# parport.net
KiCad netlist of a schematic drawn in EAGLE
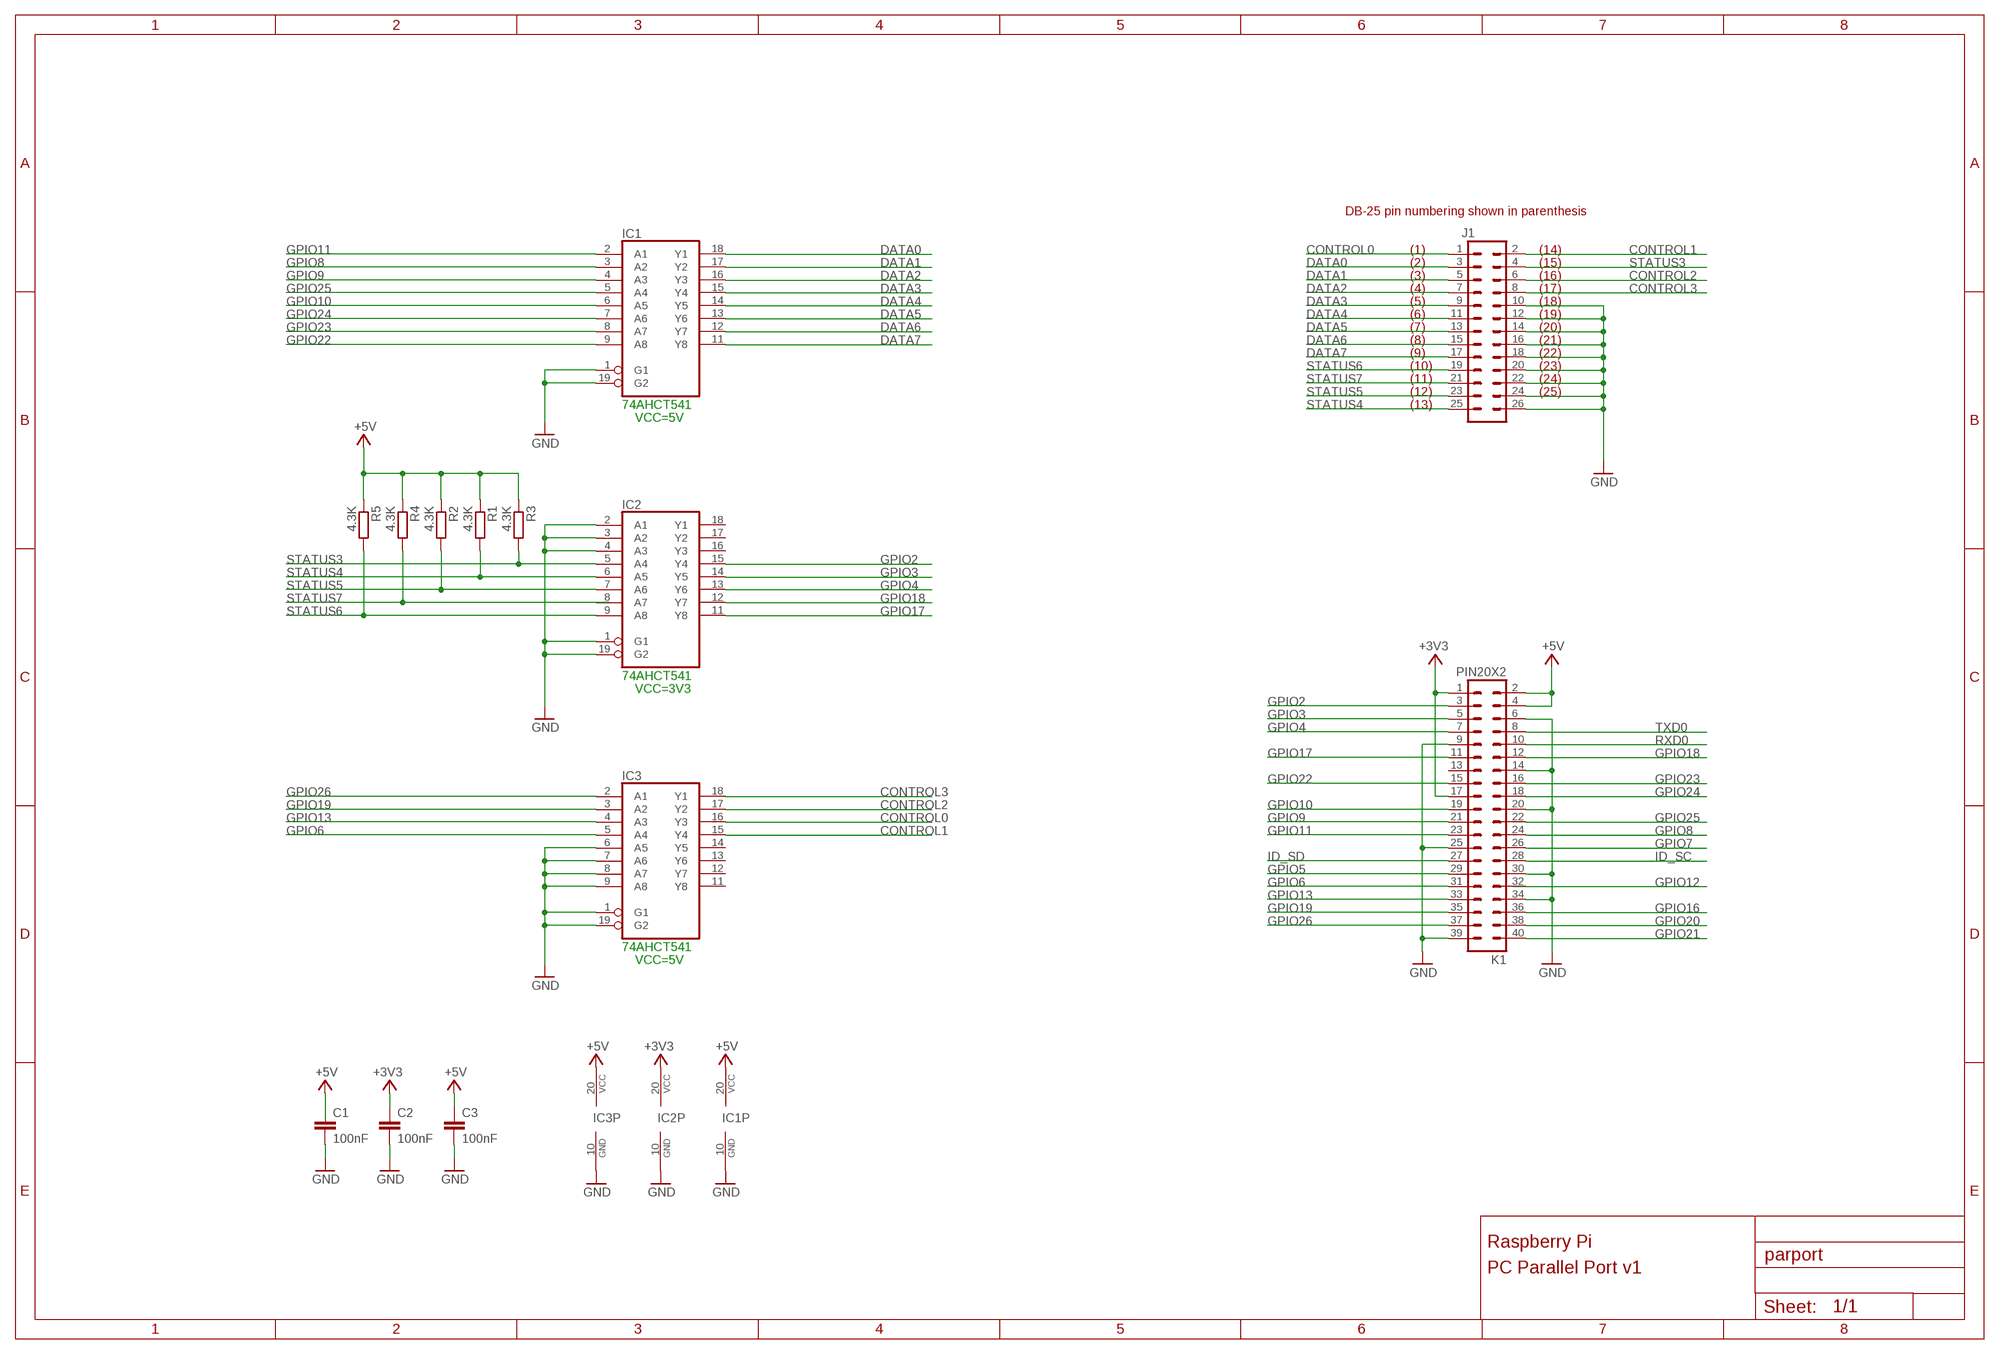
[diagram p0: schematic, sheet 1]

(export (version "E")
  (design (tool "Eeschema 10.0.6"))
  (components
    (comp (ref "C1")
      (value "100nF")
      (footprint "eagle-import:C0805")
      (libsource (lib "eagle-import") (part "C-EUC0805"))
    )
    (comp (ref "C2")
      (value "100nF")
      (footprint "eagle-import:C0805")
      (libsource (lib "eagle-import") (part "C-EUC0805"))
    )
    (comp (ref "C3")
      (value "100nF")
      (footprint "eagle-import:C0805")
      (libsource (lib "eagle-import") (part "C-EUC0805"))
    )
    (comp (ref "IC1")
      (value "74LS541DW")
      (footprint "eagle-import:SO20W")
      (libsource (lib "eagle-import") (part "74541DWLS"))
    )
    (comp (ref "IC2")
      (value "74LS541DW")
      (footprint "eagle-import:SO20W")
      (libsource (lib "eagle-import") (part "74541DWLS"))
    )
    (comp (ref "IC3")
      (value "74LS541DW")
      (footprint "eagle-import:SO20W")
      (libsource (lib "eagle-import") (part "74541DWLS"))
    )
    (comp (ref "J1")
      (value "M13X22X13")
      (footprint "eagle-import:2X13")
      (libsource (lib "eagle-import") (part "M13X22X13"))
    )
    (comp (ref "K1")
      (value "PIN20X2")
      (footprint "eagle-import:PIN_20X2")
      (libsource (lib "eagle-import") (part "PIN20X2"))
    )
    (comp (ref "R1")
      (value "4.3K")
      (footprint "eagle-import:R0805")
      (libsource (lib "eagle-import") (part "R-EU_R0805"))
    )
    (comp (ref "R2")
      (value "4.3K")
      (footprint "eagle-import:R0805")
      (libsource (lib "eagle-import") (part "R-EU_R0805"))
    )
    (comp (ref "R3")
      (value "4.3K")
      (footprint "eagle-import:R0805")
      (libsource (lib "eagle-import") (part "R-EU_R0805"))
    )
    (comp (ref "R4")
      (value "4.3K")
      (footprint "eagle-import:R0805")
      (libsource (lib "eagle-import") (part "R-EU_R0805"))
    )
    (comp (ref "R5")
      (value "4.3K")
      (footprint "eagle-import:R0805")
      (libsource (lib "eagle-import") (part "R-EU_R0805"))
    )
  )
  (nets
    (net (code "1") (name "+3V3") (class "Default")
      (node (ref "C2") (pin "1") (pinfunction "1_1") (pintype "passive"))
      (node (ref "IC2") (pin "20") (pinfunction "VCC_20") (pintype "power_in"))
      (node (ref "K1") (pin "1") (pinfunction "1_1") (pintype "passive"))
      (node (ref "K1") (pin "17") (pinfunction "17_17") (pintype "passive"))
    )
    (net (code "2") (name "+5V") (class "Default")
      (node (ref "C1") (pin "1") (pinfunction "1_1") (pintype "passive"))
      (node (ref "C3") (pin "1") (pinfunction "1_1") (pintype "passive"))
      (node (ref "IC1") (pin "20") (pinfunction "VCC_20") (pintype "power_in"))
      (node (ref "IC3") (pin "20") (pinfunction "VCC_20") (pintype "power_in"))
      (node (ref "K1") (pin "2") (pinfunction "2_2") (pintype "passive"))
      (node (ref "K1") (pin "4") (pinfunction "4_4") (pintype "passive"))
      (node (ref "R1") (pin "1") (pinfunction "1_1") (pintype "passive"))
      (node (ref "R2") (pin "1") (pinfunction "1_1") (pintype "passive"))
      (node (ref "R3") (pin "1") (pinfunction "1_1") (pintype "passive"))
      (node (ref "R4") (pin "1") (pinfunction "1_1") (pintype "passive"))
      (node (ref "R5") (pin "1") (pinfunction "1_1") (pintype "passive"))
    )
    (net (code "3") (name "/CONTROL0") (class "Default")
      (node (ref "IC3") (pin "16") (pinfunction "Y3_16") (pintype "tri_state"))
      (node (ref "J1") (pin "1") (pinfunction "1_1") (pintype "passive"))
    )
    (net (code "4") (name "/CONTROL1") (class "Default")
      (node (ref "IC3") (pin "15") (pinfunction "Y4_15") (pintype "tri_state"))
      (node (ref "J1") (pin "2") (pinfunction "2_2") (pintype "passive"))
    )
    (net (code "5") (name "/CONTROL2") (class "Default")
      (node (ref "IC3") (pin "17") (pinfunction "Y2_17") (pintype "tri_state"))
      (node (ref "J1") (pin "6") (pinfunction "6_6") (pintype "passive"))
    )
    (net (code "6") (name "/CONTROL3") (class "Default")
      (node (ref "IC3") (pin "18") (pinfunction "Y1_18") (pintype "tri_state"))
      (node (ref "J1") (pin "8") (pinfunction "8_8") (pintype "passive"))
    )
    (net (code "7") (name "/DATA0") (class "Default")
      (node (ref "IC1") (pin "18") (pinfunction "Y1_18") (pintype "tri_state"))
      (node (ref "J1") (pin "3") (pinfunction "3_3") (pintype "passive"))
    )
    (net (code "8") (name "/DATA1") (class "Default")
      (node (ref "IC1") (pin "17") (pinfunction "Y2_17") (pintype "tri_state"))
      (node (ref "J1") (pin "5") (pinfunction "5_5") (pintype "passive"))
    )
    (net (code "9") (name "/DATA2") (class "Default")
      (node (ref "IC1") (pin "16") (pinfunction "Y3_16") (pintype "tri_state"))
      (node (ref "J1") (pin "7") (pinfunction "7_7") (pintype "passive"))
    )
    (net (code "10") (name "/DATA3") (class "Default")
      (node (ref "IC1") (pin "15") (pinfunction "Y4_15") (pintype "tri_state"))
      (node (ref "J1") (pin "9") (pinfunction "9_9") (pintype "passive"))
    )
    (net (code "11") (name "/DATA4") (class "Default")
      (node (ref "IC1") (pin "14") (pinfunction "Y5_14") (pintype "tri_state"))
      (node (ref "J1") (pin "11") (pinfunction "11_11") (pintype "passive"))
    )
    (net (code "12") (name "/DATA5") (class "Default")
      (node (ref "IC1") (pin "13") (pinfunction "Y6_13") (pintype "tri_state"))
      (node (ref "J1") (pin "13") (pinfunction "13_13") (pintype "passive"))
    )
    (net (code "13") (name "/DATA6") (class "Default")
      (node (ref "IC1") (pin "12") (pinfunction "Y7_12") (pintype "tri_state"))
      (node (ref "J1") (pin "15") (pinfunction "15_15") (pintype "passive"))
    )
    (net (code "14") (name "/DATA7") (class "Default")
      (node (ref "IC1") (pin "11") (pinfunction "Y8_11") (pintype "tri_state"))
      (node (ref "J1") (pin "17") (pinfunction "17_17") (pintype "passive"))
    )
    (net (code "15") (name "/GPIO2") (class "Default")
      (node (ref "IC2") (pin "15") (pinfunction "Y4_15") (pintype "tri_state"))
      (node (ref "K1") (pin "3") (pinfunction "3_3") (pintype "passive"))
    )
    (net (code "16") (name "/GPIO3") (class "Default")
      (node (ref "IC2") (pin "14") (pinfunction "Y5_14") (pintype "tri_state"))
      (node (ref "K1") (pin "5") (pinfunction "5_5") (pintype "passive"))
    )
    (net (code "17") (name "/GPIO4") (class "Default")
      (node (ref "IC2") (pin "13") (pinfunction "Y6_13") (pintype "tri_state"))
      (node (ref "K1") (pin "7") (pinfunction "7_7") (pintype "passive"))
    )
    (net (code "18") (name "/GPIO5") (class "Default")
      (node (ref "K1") (pin "29") (pinfunction "29_29") (pintype "passive"))
    )
    (net (code "19") (name "/GPIO6") (class "Default")
      (node (ref "IC3") (pin "5") (pinfunction "A4_5") (pintype "input"))
      (node (ref "K1") (pin "31") (pinfunction "31_31") (pintype "passive"))
    )
    (net (code "20") (name "/GPIO7") (class "Default")
      (node (ref "K1") (pin "26") (pinfunction "26_26") (pintype "passive"))
    )
    (net (code "21") (name "/GPIO8") (class "Default")
      (node (ref "IC1") (pin "3") (pinfunction "A2_3") (pintype "input"))
      (node (ref "K1") (pin "24") (pinfunction "24_24") (pintype "passive"))
    )
    (net (code "22") (name "/GPIO9") (class "Default")
      (node (ref "IC1") (pin "4") (pinfunction "A3_4") (pintype "input"))
      (node (ref "K1") (pin "21") (pinfunction "21_21") (pintype "passive"))
    )
    (net (code "23") (name "/GPIO10") (class "Default")
      (node (ref "IC1") (pin "6") (pinfunction "A5_6") (pintype "input"))
      (node (ref "K1") (pin "19") (pinfunction "19_19") (pintype "passive"))
    )
    (net (code "24") (name "/GPIO11") (class "Default")
      (node (ref "IC1") (pin "2") (pinfunction "A1_2") (pintype "input"))
      (node (ref "K1") (pin "23") (pinfunction "23_23") (pintype "passive"))
    )
    (net (code "26") (name "/GPIO13") (class "Default")
      (node (ref "IC3") (pin "4") (pinfunction "A3_4") (pintype "input"))
      (node (ref "K1") (pin "33") (pinfunction "33_33") (pintype "passive"))
    )
    (net (code "27") (name "/GPIO16") (class "Default")
      (node (ref "K1") (pin "36") (pinfunction "36_36") (pintype "passive"))
    )
    (net (code "28") (name "/GPIO17") (class "Default")
      (node (ref "IC2") (pin "11") (pinfunction "Y8_11") (pintype "tri_state"))
      (node (ref "K1") (pin "11") (pinfunction "11_11") (pintype "passive"))
    )
    (net (code "29") (name "/GPIO18") (class "Default")
      (node (ref "IC2") (pin "12") (pinfunction "Y7_12") (pintype "tri_state"))
      (node (ref "K1") (pin "12") (pinfunction "12_12") (pintype "passive"))
    )
    (net (code "30") (name "/GPIO19") (class "Default")
      (node (ref "IC3") (pin "3") (pinfunction "A2_3") (pintype "input"))
      (node (ref "K1") (pin "35") (pinfunction "35_35") (pintype "passive"))
    )
    (net (code "31") (name "/GPIO20") (class "Default")
      (node (ref "K1") (pin "38") (pinfunction "38_38") (pintype "passive"))
    )
    (net (code "32") (name "/GPIO21") (class "Default")
      (node (ref "K1") (pin "40") (pinfunction "40_40") (pintype "passive"))
    )
    (net (code "33") (name "/GPIO22") (class "Default")
      (node (ref "IC1") (pin "9") (pinfunction "A8_9") (pintype "input"))
      (node (ref "K1") (pin "15") (pinfunction "15_15") (pintype "passive"))
    )
    (net (code "34") (name "/GPIO23") (class "Default")
      (node (ref "IC1") (pin "8") (pinfunction "A7_8") (pintype "input"))
      (node (ref "K1") (pin "16") (pinfunction "16_16") (pintype "passive"))
    )
    (net (code "35") (name "/GPIO24") (class "Default")
      (node (ref "IC1") (pin "7") (pinfunction "A6_7") (pintype "input"))
      (node (ref "K1") (pin "18") (pinfunction "18_18") (pintype "passive"))
    )
    (net (code "36") (name "/GPIO25") (class "Default")
      (node (ref "IC1") (pin "5") (pinfunction "A4_5") (pintype "input"))
      (node (ref "K1") (pin "22") (pinfunction "22_22") (pintype "passive"))
    )
    (net (code "37") (name "/GPIO26") (class "Default")
      (node (ref "IC3") (pin "2") (pinfunction "A1_2") (pintype "input"))
      (node (ref "K1") (pin "37") (pinfunction "37_37") (pintype "passive"))
    )
    (net (code "38") (name "/ID_SC") (class "Default")
      (node (ref "K1") (pin "28") (pinfunction "28_28") (pintype "passive"))
    )
    (net (code "39") (name "/ID_SD") (class "Default")
      (node (ref "K1") (pin "27") (pinfunction "27_27") (pintype "passive"))
    )
    (net (code "40") (name "/RXD0") (class "Default")
      (node (ref "K1") (pin "10") (pinfunction "10_10") (pintype "passive"))
    )
    (net (code "41") (name "/STATUS3") (class "Default")
      (node (ref "IC2") (pin "5") (pinfunction "A4_5") (pintype "input"))
      (node (ref "J1") (pin "4") (pinfunction "4_4") (pintype "passive"))
      (node (ref "R3") (pin "2") (pinfunction "2_2") (pintype "passive"))
    )
    (net (code "42") (name "/STATUS4") (class "Default")
      (node (ref "IC2") (pin "6") (pinfunction "A5_6") (pintype "input"))
      (node (ref "J1") (pin "25") (pinfunction "25_25") (pintype "passive"))
      (node (ref "R1") (pin "2") (pinfunction "2_2") (pintype "passive"))
    )
    (net (code "43") (name "/STATUS5") (class "Default")
      (node (ref "IC2") (pin "7") (pinfunction "A6_7") (pintype "input"))
      (node (ref "J1") (pin "23") (pinfunction "23_23") (pintype "passive"))
      (node (ref "R2") (pin "2") (pinfunction "2_2") (pintype "passive"))
    )
    (net (code "44") (name "/STATUS6") (class "Default")
      (node (ref "IC2") (pin "9") (pinfunction "A8_9") (pintype "input"))
      (node (ref "J1") (pin "19") (pinfunction "19_19") (pintype "passive"))
      (node (ref "R5") (pin "2") (pinfunction "2_2") (pintype "passive"))
    )
    (net (code "45") (name "/STATUS7") (class "Default")
      (node (ref "IC2") (pin "8") (pinfunction "A7_8") (pintype "input"))
      (node (ref "J1") (pin "21") (pinfunction "21_21") (pintype "passive"))
      (node (ref "R4") (pin "2") (pinfunction "2_2") (pintype "passive"))
    )
    (net (code "46") (name "/TXD0") (class "Default")
      (node (ref "K1") (pin "8") (pinfunction "8_8") (pintype "passive"))
    )
    (net (code "47") (name "GND") (class "Default")
      (node (ref "C1") (pin "2") (pinfunction "2_2") (pintype "passive"))
      (node (ref "C2") (pin "2") (pinfunction "2_2") (pintype "passive"))
      (node (ref "C3") (pin "2") (pinfunction "2_2") (pintype "passive"))
      (node (ref "IC1") (pin "1") (pinfunction "G1_1") (pintype "input"))
      (node (ref "IC1") (pin "10") (pinfunction "GND_10") (pintype "power_in"))
      (node (ref "IC1") (pin "19") (pinfunction "G2_19") (pintype "input"))
      (node (ref "IC2") (pin "1") (pinfunction "G1_1") (pintype "input"))
      (node (ref "IC2") (pin "10") (pinfunction "GND_10") (pintype "power_in"))
      (node (ref "IC2") (pin "19") (pinfunction "G2_19") (pintype "input"))
      (node (ref "IC2") (pin "2") (pinfunction "A1_2") (pintype "input"))
      (node (ref "IC2") (pin "3") (pinfunction "A2_3") (pintype "input"))
      (node (ref "IC2") (pin "4") (pinfunction "A3_4") (pintype "input"))
      (node (ref "IC3") (pin "1") (pinfunction "G1_1") (pintype "input"))
      (node (ref "IC3") (pin "10") (pinfunction "GND_10") (pintype "power_in"))
      (node (ref "IC3") (pin "19") (pinfunction "G2_19") (pintype "input"))
      (node (ref "IC3") (pin "6") (pinfunction "A5_6") (pintype "input"))
      (node (ref "IC3") (pin "7") (pinfunction "A6_7") (pintype "input"))
      (node (ref "IC3") (pin "8") (pinfunction "A7_8") (pintype "input"))
      (node (ref "IC3") (pin "9") (pinfunction "A8_9") (pintype "input"))
      (node (ref "J1") (pin "10") (pinfunction "10_10") (pintype "passive"))
      (node (ref "J1") (pin "12") (pinfunction "12_12") (pintype "passive"))
      (node (ref "J1") (pin "14") (pinfunction "14_14") (pintype "passive"))
      (node (ref "J1") (pin "16") (pinfunction "16_16") (pintype "passive"))
      (node (ref "J1") (pin "18") (pinfunction "18_18") (pintype "passive"))
      (node (ref "J1") (pin "20") (pinfunction "20_20") (pintype "passive"))
      (node (ref "J1") (pin "22") (pinfunction "22_22") (pintype "passive"))
      (node (ref "J1") (pin "24") (pinfunction "24_24") (pintype "passive"))
      (node (ref "J1") (pin "26") (pinfunction "26_26") (pintype "passive"))
      (node (ref "K1") (pin "14") (pinfunction "14_14") (pintype "passive"))
      (node (ref "K1") (pin "20") (pinfunction "20_20") (pintype "passive"))
      (node (ref "K1") (pin "25") (pinfunction "25_25") (pintype "passive"))
      (node (ref "K1") (pin "30") (pinfunction "30_30") (pintype "passive"))
      (node (ref "K1") (pin "34") (pinfunction "34_34") (pintype "passive"))
      (node (ref "K1") (pin "39") (pinfunction "39_39") (pintype "passive"))
      (node (ref "K1") (pin "6") (pinfunction "6_6") (pintype "passive"))
      (node (ref "K1") (pin "9") (pinfunction "9_9") (pintype "passive"))
    )
    (net (code "48") (name "unconnected-(IC2A-Y1-Pad18)") (class "Default")
      (node (ref "IC2") (pin "18") (pinfunction "Y1_18") (pintype "tri_state"))
    )
    (net (code "49") (name "unconnected-(IC2A-Y2-Pad17)") (class "Default")
      (node (ref "IC2") (pin "17") (pinfunction "Y2_17") (pintype "tri_state"))
    )
    (net (code "50") (name "unconnected-(IC2A-Y3-Pad16)") (class "Default")
      (node (ref "IC2") (pin "16") (pinfunction "Y3_16") (pintype "tri_state"))
    )
    (net (code "51") (name "unconnected-(IC3A-Y5-Pad14)") (class "Default")
      (node (ref "IC3") (pin "14") (pinfunction "Y5_14") (pintype "tri_state"))
    )
    (net (code "52") (name "unconnected-(IC3A-Y6-Pad13)") (class "Default")
      (node (ref "IC3") (pin "13") (pinfunction "Y6_13") (pintype "tri_state"))
    )
    (net (code "53") (name "unconnected-(IC3A-Y7-Pad12)") (class "Default")
      (node (ref "IC3") (pin "12") (pinfunction "Y7_12") (pintype "tri_state"))
    )
    (net (code "54") (name "unconnected-(IC3A-Y8-Pad11)") (class "Default")
      (node (ref "IC3") (pin "11") (pinfunction "Y8_11") (pintype "tri_state"))
    )
    (net (code "55") (name "unconnected-(K1-Pad13)") (class "Default")
      (node (ref "K1") (pin "13") (pinfunction "13_13") (pintype "passive"))
    )
    (net (code "56") (name "unconnected-(K1-Pad32)") (class "Default")
      (node (ref "K1") (pin "32") (pinfunction "32_32") (pintype "passive"))
    )
  )
)
